# FingerPrint.net
KiCad netlist of a schematic drawn in Altium Designer
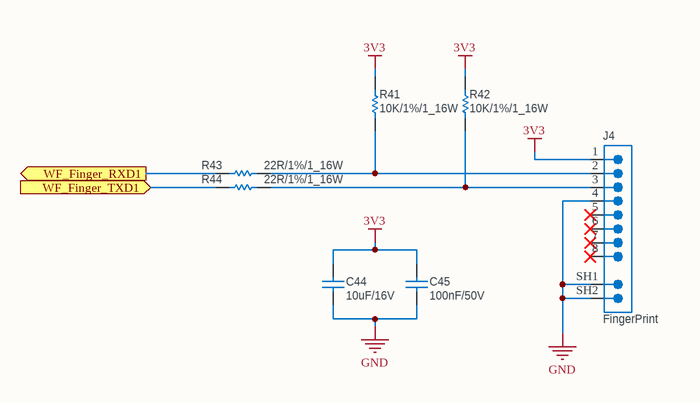
[diagram p0: FingerPrint.SchDoc]

(export (version "E")
  (design (tool "Eeschema 10.0.6"))
  (components
    (comp (ref "C44")
      (value "10uF/16V")
      (footprint "CAP_0603")
      (description "CAP, size 0603, 10uF, 16V")
      (fields (field (name "SUPPLY PART NUMBER") "Tụ Gốm 0603 10uF 16V"))
      (libsource (lib "BluetoothTracking") (part "Ceramic_Cap_10uF_16V_0603"))
    )
    (comp (ref "C45")
      (value "100nF/50V")
      (footprint "CAP_0603")
      (description "CAP, size 0603, 100nF, 50V")
      (fields (field (name "SUPPLY PART NUMBER") "Tụ Gốm 0603 100nF (0.1uF) 50V"))
      (libsource (lib "BluetoothTracking") (part "Ceramic_Cap_100nF_50V_0603"))
    )
    (comp (ref "J4")
      (value "FingerPrint")
      (footprint "MX_1.25mm_8P")
      (description "Đầu MX1.25mm 8 Chân Dán SMD Thẳng Đứng")
      (libsource (lib "BluetoothTracking") (part "MX_1.25mm_8P"))
    )
    (comp (ref "R41")
      (value "10K/1%/1_16W")
      (footprint "RESISTOR_0402")
      (description "Resistor 0402 10KOhm 1% 1_16W")
      (fields (field (name "SUPPLY PART NUMBER") "Điện Trở 10 KOhm 0402 1%"))
      (libsource (lib "BluetoothTracking") (part "Res_10K_0402_1%"))
    )
    (comp (ref "R42")
      (value "10K/1%/1_16W")
      (footprint "RESISTOR_0402")
      (description "Resistor 0402 10KOhm 1% 1_16W")
      (fields (field (name "SUPPLY PART NUMBER") "Điện Trở 10 KOhm 0402 1%"))
      (libsource (lib "BluetoothTracking") (part "Res_10K_0402_1%"))
    )
    (comp (ref "R43")
      (value "22R/1%/1_16W")
      (footprint "RESISTOR_0402")
      (description "Resistor 0402 22 Ohm 1% 1_16W")
      (libsource (lib "BluetoothTracking") (part "Res_22R_0402_1%"))
    )
    (comp (ref "R44")
      (value "22R/1%/1_16W")
      (footprint "RESISTOR_0402")
      (description "Resistor 0402 22 Ohm 1% 1_16W")
      (libsource (lib "BluetoothTracking") (part "Res_22R_0402_1%"))
    )
  )
  (nets
    (net (code "1") (name "/WF_Finger_RXD1") (class "Default")
      (node (ref "R43") (pin "1") (pinfunction "1_1") (pintype "passive"))
    )
    (net (code "2") (name "/WF_Finger_TXD1") (class "Default")
      (node (ref "R44") (pin "1") (pinfunction "1_1") (pintype "passive"))
    )
    (net (code "3") (name "3V3") (class "Default")
      (node (ref "C44") (pin "2") (pinfunction "2_2") (pintype "passive"))
      (node (ref "C45") (pin "2") (pinfunction "2_2") (pintype "passive"))
      (node (ref "J4") (pin "1") (pinfunction "1_1") (pintype "passive"))
      (node (ref "R41") (pin "2") (pinfunction "2_2") (pintype "passive"))
      (node (ref "R42") (pin "2") (pinfunction "2_2") (pintype "passive"))
    )
    (net (code "4") (name "GND") (class "Default")
      (node (ref "C44") (pin "1") (pinfunction "1_1") (pintype "passive"))
      (node (ref "C45") (pin "1") (pinfunction "1_1") (pintype "passive"))
      (node (ref "J4") (pin "4") (pinfunction "4_4") (pintype "passive"))
      (node (ref "J4") (pin "SH1") (pinfunction "SHIELD_SH1") (pintype "passive"))
      (node (ref "J4") (pin "SH2") (pinfunction "SHIELD_SH2") (pintype "passive"))
    )
    (net (code "5") (name "Net-(J4-Pad2)") (class "Default")
      (node (ref "J4") (pin "2") (pinfunction "2_2") (pintype "passive"))
      (node (ref "R41") (pin "1") (pinfunction "1_1") (pintype "passive"))
      (node (ref "R43") (pin "2") (pinfunction "2_2") (pintype "passive"))
    )
    (net (code "6") (name "Net-(J4-Pad3)") (class "Default")
      (node (ref "J4") (pin "3") (pinfunction "3_3") (pintype "passive"))
      (node (ref "R42") (pin "1") (pinfunction "1_1") (pintype "passive"))
      (node (ref "R44") (pin "2") (pinfunction "2_2") (pintype "passive"))
    )
    (net (code "7") (name "unconnected-(J4-Pad5)") (class "Default")
      (node (ref "J4") (pin "5") (pinfunction "5_5") (pintype "passive+no_connect"))
    )
    (net (code "8") (name "unconnected-(J4-Pad6)") (class "Default")
      (node (ref "J4") (pin "6") (pinfunction "6_6") (pintype "passive+no_connect"))
    )
    (net (code "9") (name "unconnected-(J4-Pad7)") (class "Default")
      (node (ref "J4") (pin "7") (pinfunction "7_7") (pintype "passive+no_connect"))
    )
    (net (code "10") (name "unconnected-(J4-Pad8)") (class "Default")
      (node (ref "J4") (pin "8") (pinfunction "8_8") (pintype "passive+no_connect"))
    )
  )
)
